# vfd.net
KiCad netlist of a schematic drawn in EAGLE
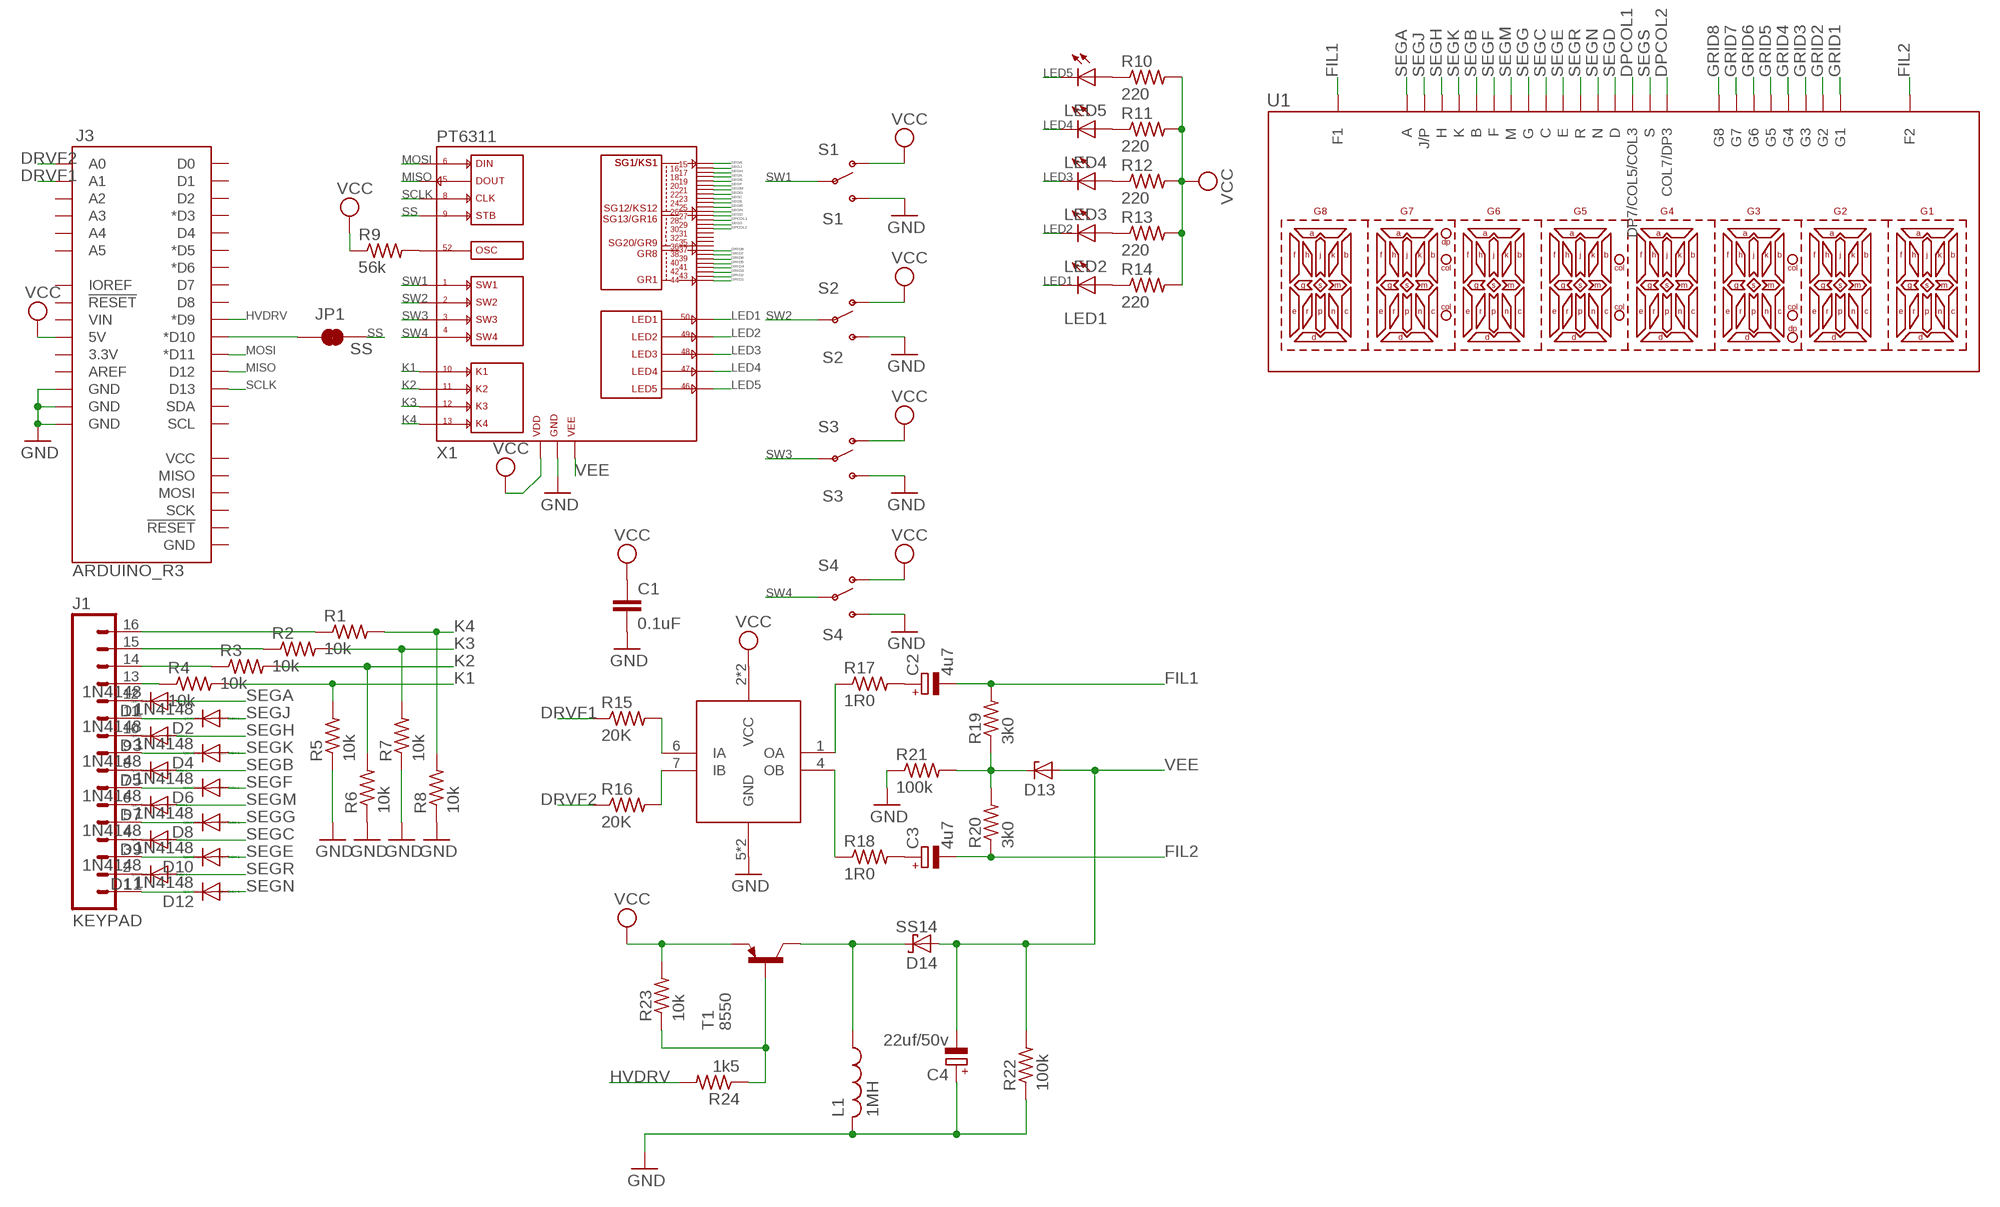
[diagram p0: schematic, sheet 1]

(export (version "E")
  (design (tool "Eeschema 10.0.6"))
  (components
    (comp (ref "C1")
      (value "0.1uF")
      (footprint "eagle-import:C050-025X075")
      (libsource (lib "eagle-import") (part "C-EU050-025X075"))
    )
    (comp (ref "C2")
      (value "4u7")
      (footprint "eagle-import:B45181A")
      (libsource (lib "eagle-import") (part "CPOL-EUB45181A"))
    )
    (comp (ref "C3")
      (value "4u7")
      (footprint "eagle-import:B45181A")
      (libsource (lib "eagle-import") (part "CPOL-EUB45181A"))
    )
    (comp (ref "C4")
      (value "22uf/50v")
      (footprint "eagle-import:B45181A")
      (libsource (lib "eagle-import") (part "CPOL-EUB45181A"))
    )
    (comp (ref "D1")
      (value "1N4148")
      (footprint "eagle-import:D-5")
      (libsource (lib "eagle-import") (part "DIODE-D-5"))
    )
    (comp (ref "D2")
      (value "1N4148")
      (footprint "eagle-import:D-5")
      (libsource (lib "eagle-import") (part "DIODE-D-5"))
    )
    (comp (ref "D3")
      (value "1N4148")
      (footprint "eagle-import:D-5")
      (libsource (lib "eagle-import") (part "DIODE-D-5"))
    )
    (comp (ref "D4")
      (value "1N4148")
      (footprint "eagle-import:D-5")
      (libsource (lib "eagle-import") (part "DIODE-D-5"))
    )
    (comp (ref "D5")
      (value "1N4148")
      (footprint "eagle-import:D-5")
      (libsource (lib "eagle-import") (part "DIODE-D-5"))
    )
    (comp (ref "D6")
      (value "1N4148")
      (footprint "eagle-import:D-5")
      (libsource (lib "eagle-import") (part "DIODE-D-5"))
    )
    (comp (ref "D7")
      (value "1N4148")
      (footprint "eagle-import:D-5")
      (libsource (lib "eagle-import") (part "DIODE-D-5"))
    )
    (comp (ref "D8")
      (value "1N4148")
      (footprint "eagle-import:D-5")
      (libsource (lib "eagle-import") (part "DIODE-D-5"))
    )
    (comp (ref "D9")
      (value "1N4148")
      (footprint "eagle-import:D-5")
      (libsource (lib "eagle-import") (part "DIODE-D-5"))
    )
    (comp (ref "D10")
      (value "1N4148")
      (footprint "eagle-import:D-5")
      (libsource (lib "eagle-import") (part "DIODE-D-5"))
    )
    (comp (ref "D11")
      (value "1N4148")
      (footprint "eagle-import:D-5")
      (libsource (lib "eagle-import") (part "DIODE-D-5"))
    )
    (comp (ref "D12")
      (value "1N4148")
      (footprint "eagle-import:D-5")
      (libsource (lib "eagle-import") (part "DIODE-D-5"))
    )
    (comp (ref "D13")
      (value "ZENER-DIODEDO34-7")
      (footprint "eagle-import:DO34Z7")
      (libsource (lib "eagle-import") (part "ZENER-DIODEDO34-7"))
    )
    (comp (ref "D14")
      (value "SS14")
      (footprint "eagle-import:DO35-7")
      (libsource (lib "eagle-import") (part "SCHOTTKY-DIODEDO35-7"))
    )
    (comp (ref "J1")
      (value "KEYPAD")
      (footprint "eagle-import:1X16")
      (libsource (lib "eagle-import") (part "M16PTH"))
    )
    (comp (ref "J3")
      (value "ARDUINO_R3")
      (footprint "eagle-import:ARDUINO_R3")
      (libsource (lib "eagle-import") (part "ARDUINO_R3"))
    )
    (comp (ref "JP1")
      (value "SS")
      (footprint "eagle-import:PAD-JUMPER-2-NC_BY_TRACE_YES_SILK")
      (libsource (lib "eagle-import") (part "JUMPER-PAD-2-NC_BY_TRACE"))
    )
    (comp (ref "L1")
      (value "1MH")
      (footprint "eagle-import:0204_5")
      (libsource (lib "eagle-import") (part "L-US0204/5"))
    )
    (comp (ref "LED1")
      (value "LED1")
      (footprint "eagle-import:LED3MM")
      (libsource (lib "eagle-import") (part "LED3MM"))
    )
    (comp (ref "LED2")
      (value "LED2")
      (footprint "eagle-import:LED3MM")
      (libsource (lib "eagle-import") (part "LED3MM"))
    )
    (comp (ref "LED3")
      (value "LED3")
      (footprint "eagle-import:LED3MM")
      (libsource (lib "eagle-import") (part "LED3MM"))
    )
    (comp (ref "LED4")
      (value "LED4")
      (footprint "eagle-import:LED3MM")
      (libsource (lib "eagle-import") (part "LED3MM"))
    )
    (comp (ref "LED5")
      (value "LED5")
      (footprint "eagle-import:LED3MM")
      (libsource (lib "eagle-import") (part "LED3MM"))
    )
    (comp (ref "R1")
      (value "10k")
      (footprint "eagle-import:0204_7")
      (libsource (lib "eagle-import") (part "R-US_0204/7"))
    )
    (comp (ref "R2")
      (value "10k")
      (footprint "eagle-import:0204_7")
      (libsource (lib "eagle-import") (part "R-US_0204/7"))
    )
    (comp (ref "R3")
      (value "10k")
      (footprint "eagle-import:0204_7")
      (libsource (lib "eagle-import") (part "R-US_0204/7"))
    )
    (comp (ref "R4")
      (value "10k")
      (footprint "eagle-import:0204_7")
      (libsource (lib "eagle-import") (part "R-US_0204/7"))
    )
    (comp (ref "R5")
      (value "10k")
      (footprint "eagle-import:0204_5")
      (libsource (lib "eagle-import") (part "R-US_0204/5"))
    )
    (comp (ref "R6")
      (value "10k")
      (footprint "eagle-import:0204_5")
      (libsource (lib "eagle-import") (part "R-US_0204/5"))
    )
    (comp (ref "R7")
      (value "10k")
      (footprint "eagle-import:0204_5")
      (libsource (lib "eagle-import") (part "R-US_0204/5"))
    )
    (comp (ref "R8")
      (value "10k")
      (footprint "eagle-import:0204_5")
      (libsource (lib "eagle-import") (part "R-US_0204/5"))
    )
    (comp (ref "R9")
      (value "56k")
      (footprint "eagle-import:0204_5")
      (libsource (lib "eagle-import") (part "R-US_0204/5"))
    )
    (comp (ref "R10")
      (value "220")
      (footprint "eagle-import:0204_5")
      (libsource (lib "eagle-import") (part "R-US_0204/5"))
    )
    (comp (ref "R11")
      (value "220")
      (footprint "eagle-import:0204_5")
      (libsource (lib "eagle-import") (part "R-US_0204/5"))
    )
    (comp (ref "R12")
      (value "220")
      (footprint "eagle-import:0204_5")
      (libsource (lib "eagle-import") (part "R-US_0204/5"))
    )
    (comp (ref "R13")
      (value "220")
      (footprint "eagle-import:0204_5")
      (libsource (lib "eagle-import") (part "R-US_0204/5"))
    )
    (comp (ref "R14")
      (value "220")
      (footprint "eagle-import:0204_5")
      (libsource (lib "eagle-import") (part "R-US_0204/5"))
    )
    (comp (ref "R15")
      (value "20K")
      (footprint "eagle-import:0204_5")
      (libsource (lib "eagle-import") (part "R-US_0204/5"))
    )
    (comp (ref "R16")
      (value "20K")
      (footprint "eagle-import:0204_5")
      (libsource (lib "eagle-import") (part "R-US_0204/5"))
    )
    (comp (ref "R17")
      (value "1R0")
      (footprint "eagle-import:0204_5")
      (libsource (lib "eagle-import") (part "R-US_0204/5"))
    )
    (comp (ref "R18")
      (value "1R0")
      (footprint "eagle-import:0204_5")
      (libsource (lib "eagle-import") (part "R-US_0204/5"))
    )
    (comp (ref "R19")
      (value "3k0")
      (footprint "eagle-import:0204_7")
      (libsource (lib "eagle-import") (part "R-US_0204/7"))
    )
    (comp (ref "R20")
      (value "3k0")
      (footprint "eagle-import:0204_7")
      (libsource (lib "eagle-import") (part "R-US_0204/7"))
    )
    (comp (ref "R21")
      (value "100k")
      (footprint "eagle-import:0204_7")
      (libsource (lib "eagle-import") (part "R-US_0204/7"))
    )
    (comp (ref "R22")
      (value "100k")
      (footprint "eagle-import:0204_5")
      (libsource (lib "eagle-import") (part "R-US_0204/5"))
    )
    (comp (ref "R23")
      (value "10k")
      (footprint "eagle-import:0204_5")
      (libsource (lib "eagle-import") (part "R-US_0204/5"))
    )
    (comp (ref "R24")
      (value "1k5")
      (footprint "eagle-import:0204_5")
      (libsource (lib "eagle-import") (part "R-US_0204/5"))
    )
    (comp (ref "S1")
      (value "S1")
      (footprint "eagle-import:SWITCH-SPDT")
      (libsource (lib "eagle-import") (part "SWITCH-SPDTPTH"))
    )
    (comp (ref "S2")
      (value "S2")
      (footprint "eagle-import:SWITCH-SPDT")
      (libsource (lib "eagle-import") (part "SWITCH-SPDTPTH"))
    )
    (comp (ref "S3")
      (value "S3")
      (footprint "eagle-import:SWITCH-SPDT")
      (libsource (lib "eagle-import") (part "SWITCH-SPDTPTH"))
    )
    (comp (ref "S4")
      (value "S4")
      (footprint "eagle-import:SWITCH-SPDT")
      (libsource (lib "eagle-import") (part "SWITCH-SPDTPTH"))
    )
    (comp (ref "T1")
      (value "8550")
      (footprint "eagle-import:TO92")
      (libsource (lib "eagle-import") (part "-PNP-TO92"))
    )
    (comp (ref "U$1")
      (value "L9110")
      (footprint "eagle-import:SOP8-1.27-5X3.6MM")
      (libsource (lib "eagle-import") (part "L9110"))
    )
    (comp (ref "U1")
      (value "20070-1A04PTH")
      (footprint "eagle-import:20070-1A04")
      (libsource (lib "eagle-import") (part "20070-1A04PTH"))
    )
    (comp (ref "X1")
      (value "DRV")
      (footprint "eagle-import:QFP52")
      (libsource (lib "eagle-import") (part "PT6311"))
    )
  )
  (nets
    (net (code "1") (name "/DPCOL1") (class "Default")
      (node (ref "U1") (pin "17") (pinfunction "DP7/COL5/COL3_17") (pintype "bidirectional"))
      (node (ref "X1") (pin "P$28") (pinfunction "SG14/GR15_P$28") (pintype "bidirectional"))
    )
    (net (code "2") (name "/DPCOL2") (class "Default")
      (node (ref "U1") (pin "19") (pinfunction "COL7/DP3_19") (pintype "bidirectional"))
      (node (ref "X1") (pin "P$30") (pinfunction "SG16/GR13_P$30") (pintype "bidirectional"))
    )
    (net (code "3") (name "/DRVF1") (class "Default")
      (node (ref "J3") (pin "A1") (pinfunction "A1_A1") (pintype "bidirectional"))
      (node (ref "R15") (pin "1") (pinfunction "1_1") (pintype "passive"))
    )
    (net (code "4") (name "/DRVF2") (class "Default")
      (node (ref "J3") (pin "A0") (pinfunction "A0_A0") (pintype "bidirectional"))
      (node (ref "R16") (pin "1") (pinfunction "1_1") (pintype "passive"))
    )
    (net (code "5") (name "/FIL1") (class "Default")
      (node (ref "C2") (pin "-") (pinfunction "-_-") (pintype "passive"))
      (node (ref "R19") (pin "2") (pinfunction "2_2") (pintype "passive"))
      (node (ref "U1") (pin "1") (pinfunction "F1_1") (pintype "bidirectional"))
      (node (ref "U1") (pin "2") (pinfunction "F1_2") (pintype "bidirectional"))
    )
    (net (code "6") (name "/FIL2") (class "Default")
      (node (ref "C3") (pin "-") (pinfunction "-_-") (pintype "passive"))
      (node (ref "R20") (pin "1") (pinfunction "1_1") (pintype "passive"))
      (node (ref "U1") (pin "29") (pinfunction "F2_29") (pintype "bidirectional"))
      (node (ref "U1") (pin "30") (pinfunction "F2_30") (pintype "bidirectional"))
    )
    (net (code "7") (name "/GRID1") (class "Default")
      (node (ref "U1") (pin "27") (pinfunction "G1_27") (pintype "bidirectional"))
      (node (ref "X1") (pin "P$44") (pinfunction "GR1_P$44") (pintype "bidirectional"))
    )
    (net (code "8") (name "/GRID2") (class "Default")
      (node (ref "U1") (pin "26") (pinfunction "G2_26") (pintype "bidirectional"))
      (node (ref "X1") (pin "P$43") (pinfunction "GR2_P$43") (pintype "bidirectional"))
    )
    (net (code "9") (name "/GRID3") (class "Default")
      (node (ref "U1") (pin "25") (pinfunction "G3_25") (pintype "bidirectional"))
      (node (ref "X1") (pin "P$42") (pinfunction "GR3_P$42") (pintype "bidirectional"))
    )
    (net (code "10") (name "/GRID4") (class "Default")
      (node (ref "U1") (pin "24") (pinfunction "G4_24") (pintype "bidirectional"))
      (node (ref "X1") (pin "P$41") (pinfunction "GR4_P$41") (pintype "bidirectional"))
    )
    (net (code "11") (name "/GRID5") (class "Default")
      (node (ref "U1") (pin "23") (pinfunction "G5_23") (pintype "bidirectional"))
      (node (ref "X1") (pin "P$40") (pinfunction "GR5_P$40") (pintype "bidirectional"))
    )
    (net (code "12") (name "/GRID6") (class "Default")
      (node (ref "U1") (pin "22") (pinfunction "G6_22") (pintype "bidirectional"))
      (node (ref "X1") (pin "P$39") (pinfunction "GR6_P$39") (pintype "bidirectional"))
    )
    (net (code "13") (name "/GRID7") (class "Default")
      (node (ref "U1") (pin "21") (pinfunction "G7_21") (pintype "bidirectional"))
      (node (ref "X1") (pin "P$38") (pinfunction "GR7_P$38") (pintype "bidirectional"))
    )
    (net (code "14") (name "/GRID8") (class "Default")
      (node (ref "U1") (pin "20") (pinfunction "G8_20") (pintype "bidirectional"))
      (node (ref "X1") (pin "P$37") (pinfunction "GR8_P$37") (pintype "bidirectional"))
    )
    (net (code "15") (name "/HVDRV") (class "Default")
      (node (ref "J3") (pin "D9") (pinfunction "*D9_D9") (pintype "bidirectional"))
      (node (ref "R24") (pin "2") (pinfunction "2_2") (pintype "passive"))
    )
    (net (code "16") (name "/K1") (class "Default")
      (node (ref "R4") (pin "2") (pinfunction "2_2") (pintype "passive"))
      (node (ref "R5") (pin "2") (pinfunction "2_2") (pintype "passive"))
      (node (ref "X1") (pin "P$10") (pinfunction "K1_P$10") (pintype "bidirectional"))
    )
    (net (code "17") (name "/K2") (class "Default")
      (node (ref "R3") (pin "2") (pinfunction "2_2") (pintype "passive"))
      (node (ref "R6") (pin "2") (pinfunction "2_2") (pintype "passive"))
      (node (ref "X1") (pin "P$11") (pinfunction "K2_P$11") (pintype "bidirectional"))
    )
    (net (code "18") (name "/K3") (class "Default")
      (node (ref "R2") (pin "2") (pinfunction "2_2") (pintype "passive"))
      (node (ref "R7") (pin "2") (pinfunction "2_2") (pintype "passive"))
      (node (ref "X1") (pin "P$12") (pinfunction "K3_P$12") (pintype "bidirectional"))
    )
    (net (code "19") (name "/K4") (class "Default")
      (node (ref "R1") (pin "2") (pinfunction "2_2") (pintype "passive"))
      (node (ref "R8") (pin "2") (pinfunction "2_2") (pintype "passive"))
      (node (ref "X1") (pin "P$13") (pinfunction "K4_P$13") (pintype "bidirectional"))
    )
    (net (code "20") (name "/LED1") (class "Default")
      (node (ref "LED1") (pin "K") (pinfunction "C_K") (pintype "passive"))
      (node (ref "X1") (pin "P$50") (pinfunction "LED1_P$50") (pintype "bidirectional"))
    )
    (net (code "21") (name "/LED2") (class "Default")
      (node (ref "LED2") (pin "K") (pinfunction "C_K") (pintype "passive"))
      (node (ref "X1") (pin "P$49") (pinfunction "LED2_P$49") (pintype "bidirectional"))
    )
    (net (code "22") (name "/LED3") (class "Default")
      (node (ref "LED3") (pin "K") (pinfunction "C_K") (pintype "passive"))
      (node (ref "X1") (pin "P$48") (pinfunction "LED3_P$48") (pintype "bidirectional"))
    )
    (net (code "23") (name "/LED4") (class "Default")
      (node (ref "LED4") (pin "K") (pinfunction "C_K") (pintype "passive"))
      (node (ref "X1") (pin "P$47") (pinfunction "LED4_P$47") (pintype "bidirectional"))
    )
    (net (code "24") (name "/LED5") (class "Default")
      (node (ref "LED5") (pin "K") (pinfunction "C_K") (pintype "passive"))
      (node (ref "X1") (pin "P$46") (pinfunction "LED5_P$46") (pintype "bidirectional"))
    )
    (net (code "25") (name "/MISO") (class "Default")
      (node (ref "J3") (pin "D12") (pinfunction "D12_D12") (pintype "bidirectional"))
      (node (ref "X1") (pin "P$5") (pinfunction "DOUT_P$5") (pintype "bidirectional"))
    )
    (net (code "26") (name "/MOSI") (class "Default")
      (node (ref "J3") (pin "D11") (pinfunction "*D11_D11") (pintype "bidirectional"))
      (node (ref "X1") (pin "P$6") (pinfunction "DIN_P$6") (pintype "bidirectional"))
    )
    (net (code "27") (name "/SCLK") (class "Default")
      (node (ref "J3") (pin "D13") (pinfunction "D13_D13") (pintype "bidirectional"))
      (node (ref "X1") (pin "P$8") (pinfunction "CLK_P$8") (pintype "bidirectional"))
    )
    (net (code "28") (name "/SEGA") (class "Default")
      (node (ref "D1") (pin "A") (pinfunction "A_A") (pintype "passive"))
      (node (ref "U1") (pin "4") (pinfunction "A_4") (pintype "bidirectional"))
      (node (ref "X1") (pin "P$15") (pinfunction "SG1/KS1_P$15") (pintype "bidirectional"))
    )
    (net (code "29") (name "/SEGB") (class "Default")
      (node (ref "D5") (pin "A") (pinfunction "A_A") (pintype "passive"))
      (node (ref "U1") (pin "8") (pinfunction "B_8") (pintype "bidirectional"))
      (node (ref "X1") (pin "P$19") (pinfunction "SG5/KS5_P$19") (pintype "bidirectional"))
    )
    (net (code "30") (name "/SEGC") (class "Default")
      (node (ref "D9") (pin "A") (pinfunction "A_A") (pintype "passive"))
      (node (ref "U1") (pin "12") (pinfunction "C_12") (pintype "bidirectional"))
      (node (ref "X1") (pin "P$23") (pinfunction "SG9/KS9_P$23") (pintype "bidirectional"))
    )
    (net (code "31") (name "/SEGD") (class "Default")
      (node (ref "U1") (pin "16") (pinfunction "D_16") (pintype "bidirectional"))
      (node (ref "X1") (pin "P$27") (pinfunction "SG13/GR16_P$27") (pintype "bidirectional"))
    )
    (net (code "32") (name "/SEGE") (class "Default")
      (node (ref "D10") (pin "A") (pinfunction "A_A") (pintype "passive"))
      (node (ref "U1") (pin "13") (pinfunction "E_13") (pintype "bidirectional"))
      (node (ref "X1") (pin "P$24") (pinfunction "SG10/KS10_P$24") (pintype "bidirectional"))
    )
    (net (code "33") (name "/SEGF") (class "Default")
      (node (ref "D6") (pin "A") (pinfunction "A_A") (pintype "passive"))
      (node (ref "U1") (pin "9") (pinfunction "F_9") (pintype "bidirectional"))
      (node (ref "X1") (pin "P$20") (pinfunction "SG6/KS6_P$20") (pintype "bidirectional"))
    )
    (net (code "34") (name "/SEGG") (class "Default")
      (node (ref "D8") (pin "A") (pinfunction "A_A") (pintype "passive"))
      (node (ref "U1") (pin "11") (pinfunction "G_11") (pintype "bidirectional"))
      (node (ref "X1") (pin "P$22") (pinfunction "SG8/KS8_P$22") (pintype "bidirectional"))
    )
    (net (code "35") (name "/SEGH") (class "Default")
      (node (ref "D3") (pin "A") (pinfunction "A_A") (pintype "passive"))
      (node (ref "U1") (pin "6") (pinfunction "H_6") (pintype "bidirectional"))
      (node (ref "X1") (pin "P$17") (pinfunction "SG3/KS3_P$17") (pintype "bidirectional"))
    )
    (net (code "36") (name "/SEGJ") (class "Default")
      (node (ref "D2") (pin "A") (pinfunction "A_A") (pintype "passive"))
      (node (ref "U1") (pin "5") (pinfunction "J/P_5") (pintype "bidirectional"))
      (node (ref "X1") (pin "P$16") (pinfunction "SG2/KS2_P$16") (pintype "bidirectional"))
    )
    (net (code "37") (name "/SEGK") (class "Default")
      (node (ref "D4") (pin "A") (pinfunction "A_A") (pintype "passive"))
      (node (ref "U1") (pin "7") (pinfunction "K_7") (pintype "bidirectional"))
      (node (ref "X1") (pin "P$18") (pinfunction "SG4/KS4_P$18") (pintype "bidirectional"))
    )
    (net (code "38") (name "/SEGM") (class "Default")
      (node (ref "D7") (pin "A") (pinfunction "A_A") (pintype "passive"))
      (node (ref "U1") (pin "10") (pinfunction "M_10") (pintype "bidirectional"))
      (node (ref "X1") (pin "P$21") (pinfunction "SG7/KS7_P$21") (pintype "bidirectional"))
    )
    (net (code "39") (name "/SEGN") (class "Default")
      (node (ref "D12") (pin "A") (pinfunction "A_A") (pintype "passive"))
      (node (ref "U1") (pin "15") (pinfunction "N_15") (pintype "bidirectional"))
      (node (ref "X1") (pin "P$26") (pinfunction "SG12/KS12_P$26") (pintype "bidirectional"))
    )
    (net (code "40") (name "/SEGR") (class "Default")
      (node (ref "D11") (pin "A") (pinfunction "A_A") (pintype "passive"))
      (node (ref "U1") (pin "14") (pinfunction "R_14") (pintype "bidirectional"))
      (node (ref "X1") (pin "P$25") (pinfunction "SG11/KS11_P$25") (pintype "bidirectional"))
    )
    (net (code "41") (name "/SEGS") (class "Default")
      (node (ref "U1") (pin "18") (pinfunction "S_18") (pintype "bidirectional"))
      (node (ref "X1") (pin "P$29") (pinfunction "SG15/GR14_P$29") (pintype "bidirectional"))
    )
    (net (code "42") (name "/SS") (class "Default")
      (node (ref "JP1") (pin "2") (pinfunction "2_2") (pintype "passive"))
      (node (ref "X1") (pin "P$9") (pinfunction "STB_P$9") (pintype "bidirectional"))
    )
    (net (code "43") (name "/SW1") (class "Default")
      (node (ref "S1") (pin "2") (pinfunction "P_2") (pintype "passive"))
      (node (ref "X1") (pin "P$1") (pinfunction "SW1_P$1") (pintype "bidirectional"))
    )
    (net (code "44") (name "/SW2") (class "Default")
      (node (ref "S2") (pin "2") (pinfunction "P_2") (pintype "passive"))
      (node (ref "X1") (pin "P$2") (pinfunction "SW2_P$2") (pintype "bidirectional"))
    )
    (net (code "45") (name "/SW3") (class "Default")
      (node (ref "S3") (pin "2") (pinfunction "P_2") (pintype "passive"))
      (node (ref "X1") (pin "P$3") (pinfunction "SW3_P$3") (pintype "bidirectional"))
    )
    (net (code "46") (name "/SW4") (class "Default")
      (node (ref "S4") (pin "2") (pinfunction "P_2") (pintype "passive"))
      (node (ref "X1") (pin "P$4") (pinfunction "SW4_P$4") (pintype "bidirectional"))
    )
    (net (code "47") (name "/VEE") (class "Default")
      (node (ref "C4") (pin "-") (pinfunction "-_-") (pintype "passive"))
      (node (ref "D13") (pin "A") (pinfunction "A_A") (pintype "passive"))
      (node (ref "D14") (pin "A") (pinfunction "A_A") (pintype "passive"))
      (node (ref "R22") (pin "2") (pinfunction "2_2") (pintype "passive"))
      (node (ref "X1") (pin "P$34") (pinfunction "VEE_P$34") (pintype "bidirectional"))
    )
    (net (code "48") (name "GND") (class "Default")
      (node (ref "C1") (pin "2") (pinfunction "2_2") (pintype "passive"))
      (node (ref "C4") (pin "+") (pinfunction "+_+") (pintype "passive"))
      (node (ref "J3") (pin "GND@2") (pinfunction "GND_GND@2") (pintype "bidirectional"))
      (node (ref "J3") (pin "GND@3") (pinfunction "GND_GND@3") (pintype "bidirectional"))
      (node (ref "J3") (pin "GND@4") (pinfunction "GND_GND@4") (pintype "bidirectional"))
      (node (ref "L1") (pin "2") (pinfunction "2_2") (pintype "passive"))
      (node (ref "R21") (pin "1") (pinfunction "1_1") (pintype "passive"))
      (node (ref "R22") (pin "1") (pinfunction "1_1") (pintype "passive"))
      (node (ref "R5") (pin "1") (pinfunction "1_1") (pintype "passive"))
      (node (ref "R6") (pin "1") (pinfunction "1_1") (pintype "passive"))
      (node (ref "R7") (pin "1") (pinfunction "1_1") (pintype "passive"))
      (node (ref "R8") (pin "1") (pinfunction "1_1") (pintype "passive"))
      (node (ref "S1") (pin "3") (pinfunction "S_3") (pintype "passive"))
      (node (ref "S2") (pin "3") (pinfunction "S_3") (pintype "passive"))
      (node (ref "S3") (pin "3") (pinfunction "S_3") (pintype "passive"))
      (node (ref "S4") (pin "3") (pinfunction "S_3") (pintype "passive"))
      (node (ref "U$1") (pin "5") (pinfunction "GND_5") (pintype "bidirectional"))
      (node (ref "U$1") (pin "8") (pinfunction "GND_8") (pintype "bidirectional"))
      (node (ref "X1") (pin "P$51") (pinfunction "GND_P$51") (pintype "bidirectional"))
    )
    (net (code "49") (name "Net-(C2-Pad+)") (class "Default")
      (node (ref "C2") (pin "+") (pinfunction "+_+") (pintype "passive"))
      (node (ref "R17") (pin "2") (pinfunction "2_2") (pintype "passive"))
    )
    (net (code "50") (name "Net-(C3-Pad+)") (class "Default")
      (node (ref "C3") (pin "+") (pinfunction "+_+") (pintype "passive"))
      (node (ref "R18") (pin "2") (pinfunction "2_2") (pintype "passive"))
    )
    (net (code "51") (name "Net-(D1-PadC)") (class "Default")
      (node (ref "D1") (pin "C") (pinfunction "C_C") (pintype "passive"))
      (node (ref "J1") (pin "12") (pinfunction "12_12") (pintype "passive"))
    )
    (net (code "52") (name "Net-(D2-PadC)") (class "Default")
      (node (ref "D2") (pin "C") (pinfunction "C_C") (pintype "passive"))
      (node (ref "J1") (pin "11") (pinfunction "11_11") (pintype "passive"))
    )
    (net (code "53") (name "Net-(D3-PadC)") (class "Default")
      (node (ref "D3") (pin "C") (pinfunction "C_C") (pintype "passive"))
      (node (ref "J1") (pin "10") (pinfunction "10_10") (pintype "passive"))
    )
    (net (code "54") (name "Net-(D4-PadC)") (class "Default")
      (node (ref "D4") (pin "C") (pinfunction "C_C") (pintype "passive"))
      (node (ref "J1") (pin "9") (pinfunction "9_9") (pintype "passive"))
    )
    (net (code "55") (name "Net-(D5-PadC)") (class "Default")
      (node (ref "D5") (pin "C") (pinfunction "C_C") (pintype "passive"))
      (node (ref "J1") (pin "8") (pinfunction "8_8") (pintype "passive"))
    )
    (net (code "56") (name "Net-(D6-PadC)") (class "Default")
      (node (ref "D6") (pin "C") (pinfunction "C_C") (pintype "passive"))
      (node (ref "J1") (pin "7") (pinfunction "7_7") (pintype "passive"))
    )
    (net (code "57") (name "Net-(D7-PadC)") (class "Default")
      (node (ref "D7") (pin "C") (pinfunction "C_C") (pintype "passive"))
      (node (ref "J1") (pin "6") (pinfunction "6_6") (pintype "passive"))
    )
    (net (code "58") (name "Net-(D8-PadC)") (class "Default")
      (node (ref "D8") (pin "C") (pinfunction "C_C") (pintype "passive"))
      (node (ref "J1") (pin "5") (pinfunction "5_5") (pintype "passive"))
    )
    (net (code "59") (name "Net-(D9-PadC)") (class "Default")
      (node (ref "D9") (pin "C") (pinfunction "C_C") (pintype "passive"))
      (node (ref "J1") (pin "4") (pinfunction "4_4") (pintype "passive"))
    )
    (net (code "60") (name "Net-(D10-PadC)") (class "Default")
      (node (ref "D10") (pin "C") (pinfunction "C_C") (pintype "passive"))
      (node (ref "J1") (pin "3") (pinfunction "3_3") (pintype "passive"))
    )
    (net (code "61") (name "Net-(D11-PadC)") (class "Default")
      (node (ref "D11") (pin "C") (pinfunction "C_C") (pintype "passive"))
      (node (ref "J1") (pin "2") (pinfunction "2_2") (pintype "passive"))
    )
    (net (code "62") (name "Net-(D12-PadC)") (class "Default")
      (node (ref "D12") (pin "C") (pinfunction "C_C") (pintype "passive"))
      (node (ref "J1") (pin "1") (pinfunction "1_1") (pintype "passive"))
    )
    (net (code "63") (name "Net-(D13-PadC)") (class "Default")
      (node (ref "D13") (pin "C") (pinfunction "C_C") (pintype "passive"))
      (node (ref "R19") (pin "1") (pinfunction "1_1") (pintype "passive"))
      (node (ref "R20") (pin "2") (pinfunction "2_2") (pintype "passive"))
      (node (ref "R21") (pin "2") (pinfunction "2_2") (pintype "passive"))
    )
    (net (code "64") (name "Net-(J1-Pad13)") (class "Default")
      (node (ref "J1") (pin "13") (pinfunction "13_13") (pintype "passive"))
      (node (ref "R4") (pin "1") (pinfunction "1_1") (pintype "passive"))
    )
    (net (code "65") (name "Net-(J1-Pad14)") (class "Default")
      (node (ref "J1") (pin "14") (pinfunction "14_14") (pintype "passive"))
      (node (ref "R3") (pin "1") (pinfunction "1_1") (pintype "passive"))
    )
    (net (code "66") (name "Net-(J1-Pad15)") (class "Default")
      (node (ref "J1") (pin "15") (pinfunction "15_15") (pintype "passive"))
      (node (ref "R2") (pin "1") (pinfunction "1_1") (pintype "passive"))
    )
    (net (code "67") (name "Net-(J1-Pad16)") (class "Default")
      (node (ref "J1") (pin "16") (pinfunction "16_16") (pintype "passive"))
      (node (ref "R1") (pin "1") (pinfunction "1_1") (pintype "passive"))
    )
    (net (code "68") (name "Net-(J3-*D10)") (class "Default")
      (node (ref "J3") (pin "D10") (pinfunction "*D10_D10") (pintype "bidirectional"))
      (node (ref "JP1") (pin "1") (pinfunction "1_1") (pintype "passive"))
    )
    (net (code "69") (name "Net-(LED1-PadA)") (class "Default")
      (node (ref "LED1") (pin "A") (pinfunction "A_A") (pintype "passive"))
      (node (ref "R14") (pin "1") (pinfunction "1_1") (pintype "passive"))
    )
    (net (code "70") (name "Net-(LED2-PadA)") (class "Default")
      (node (ref "LED2") (pin "A") (pinfunction "A_A") (pintype "passive"))
      (node (ref "R13") (pin "1") (pinfunction "1_1") (pintype "passive"))
    )
    (net (code "71") (name "Net-(LED3-PadA)") (class "Default")
      (node (ref "LED3") (pin "A") (pinfunction "A_A") (pintype "passive"))
      (node (ref "R12") (pin "1") (pinfunction "1_1") (pintype "passive"))
    )
    (net (code "72") (name "Net-(LED4-PadA)") (class "Default")
      (node (ref "LED4") (pin "A") (pinfunction "A_A") (pintype "passive"))
      (node (ref "R11") (pin "1") (pinfunction "1_1") (pintype "passive"))
    )
    (net (code "73") (name "Net-(LED5-PadA)") (class "Default")
      (node (ref "LED5") (pin "A") (pinfunction "A_A") (pintype "passive"))
      (node (ref "R10") (pin "1") (pinfunction "1_1") (pintype "passive"))
    )
    (net (code "74") (name "Net-(T1-B)") (class "Default")
      (node (ref "R23") (pin "1") (pinfunction "1_1") (pintype "passive"))
      (node (ref "R24") (pin "1") (pinfunction "1_1") (pintype "passive"))
      (node (ref "T1") (pin "2") (pinfunction "B_2") (pintype "passive"))
    )
    (net (code "75") (name "Net-(T1-C)") (class "Default")
      (node (ref "D14") (pin "C") (pinfunction "C_C") (pintype "passive"))
      (node (ref "L1") (pin "1") (pinfunction "1_1") (pintype "passive"))
      (node (ref "T1") (pin "3") (pinfunction "C_3") (pintype "passive"))
    )
    (net (code "76") (name "Net-(U$1-IA)") (class "Default")
      (node (ref "R15") (pin "2") (pinfunction "2_2") (pintype "passive"))
      (node (ref "U$1") (pin "6") (pinfunction "IA_6") (pintype "bidirectional"))
    )
    (net (code "77") (name "Net-(U$1-IB)") (class "Default")
      (node (ref "R16") (pin "2") (pinfunction "2_2") (pintype "passive"))
      (node (ref "U$1") (pin "7") (pinfunction "IB_7") (pintype "bidirectional"))
    )
    (net (code "78") (name "Net-(U$1-OA)") (class "Default")
      (node (ref "R17") (pin "1") (pinfunction "1_1") (pintype "passive"))
      (node (ref "U$1") (pin "1") (pinfunction "OA_1") (pintype "bidirectional"))
    )
    (net (code "79") (name "Net-(U$1-OB)") (class "Default")
      (node (ref "R18") (pin "1") (pinfunction "1_1") (pintype "passive"))
      (node (ref "U$1") (pin "4") (pinfunction "OB_4") (pintype "bidirectional"))
    )
    (net (code "80") (name "Net-(X1-OSC)") (class "Default")
      (node (ref "R9") (pin "2") (pinfunction "2_2") (pintype "passive"))
      (node (ref "X1") (pin "P$52") (pinfunction "OSC_P$52") (pintype "bidirectional"))
    )
    (net (code "81") (name "VCC") (class "Default")
      (node (ref "C1") (pin "1") (pinfunction "1_1") (pintype "passive"))
      (node (ref "J3") (pin "5V") (pinfunction "5V_5V") (pintype "bidirectional"))
      (node (ref "R10") (pin "2") (pinfunction "2_2") (pintype "passive"))
      (node (ref "R11") (pin "2") (pinfunction "2_2") (pintype "passive"))
      (node (ref "R12") (pin "2") (pinfunction "2_2") (pintype "passive"))
      (node (ref "R13") (pin "2") (pinfunction "2_2") (pintype "passive"))
      (node (ref "R14") (pin "2") (pinfunction "2_2") (pintype "passive"))
      (node (ref "R23") (pin "2") (pinfunction "2_2") (pintype "passive"))
      (node (ref "R9") (pin "1") (pinfunction "1_1") (pintype "passive"))
      (node (ref "S1") (pin "1") (pinfunction "O_1") (pintype "passive"))
      (node (ref "S2") (pin "1") (pinfunction "O_1") (pintype "passive"))
      (node (ref "S3") (pin "1") (pinfunction "O_1") (pintype "passive"))
      (node (ref "S4") (pin "1") (pinfunction "O_1") (pintype "passive"))
      (node (ref "T1") (pin "1") (pinfunction "E_1") (pintype "passive"))
      (node (ref "U$1") (pin "2") (pinfunction "VCC_2") (pintype "bidirectional"))
      (node (ref "U$1") (pin "3") (pinfunction "VCC_3") (pintype "bidirectional"))
      (node (ref "X1") (pin "P$14") (pinfunction "VDD_P$14") (pintype "bidirectional"))
      (node (ref "X1") (pin "P$33") (pinfunction "VDD_P$33") (pintype "bidirectional"))
      (node (ref "X1") (pin "P$45") (pinfunction "VDD_P$45") (pintype "bidirectional"))
    )
    (net (code "82") (name "unconnected-(J3-*D3-PadD3)") (class "Default")
      (node (ref "J3") (pin "D3") (pinfunction "*D3_D3") (pintype "bidirectional"))
    )
    (net (code "83") (name "unconnected-(J3-*D5-PadD5)") (class "Default")
      (node (ref "J3") (pin "D5") (pinfunction "*D5_D5") (pintype "bidirectional"))
    )
    (net (code "84") (name "unconnected-(J3-*D6-PadD6)") (class "Default")
      (node (ref "J3") (pin "D6") (pinfunction "*D6_D6") (pintype "bidirectional"))
    )
    (net (code "85") (name "unconnected-(J3-GND-PadGND@1)") (class "Default")
      (node (ref "J3") (pin "GND@1") (pinfunction "GND_GND@1") (pintype "bidirectional"))
    )
    (net (code "86") (name "unconnected-(J3-Pad3.3V)") (class "Default")
      (node (ref "J3") (pin "3.3V") (pinfunction "3.3V_3.3V") (pintype "bidirectional"))
    )
    (net (code "87") (name "unconnected-(J3-PadA2)") (class "Default")
      (node (ref "J3") (pin "A2") (pinfunction "A2_A2") (pintype "bidirectional"))
    )
    (net (code "88") (name "unconnected-(J3-PadA3)") (class "Default")
      (node (ref "J3") (pin "A3") (pinfunction "A3_A3") (pintype "bidirectional"))
    )
    (net (code "89") (name "unconnected-(J3-PadA4)") (class "Default")
      (node (ref "J3") (pin "A4") (pinfunction "A4_A4") (pintype "bidirectional"))
    )
    (net (code "90") (name "unconnected-(J3-PadA5)") (class "Default")
      (node (ref "J3") (pin "A5") (pinfunction "A5_A5") (pintype "bidirectional"))
    )
    (net (code "91") (name "unconnected-(J3-PadAREF)") (class "Default")
      (node (ref "J3") (pin "AREF") (pinfunction "AREF_AREF") (pintype "bidirectional"))
    )
    (net (code "92") (name "unconnected-(J3-PadD0)") (class "Default")
      (node (ref "J3") (pin "D0") (pinfunction "D0_D0") (pintype "bidirectional"))
    )
    (net (code "93") (name "unconnected-(J3-PadD1)") (class "Default")
      (node (ref "J3") (pin "D1") (pinfunction "D1_D1") (pintype "bidirectional"))
    )
    (net (code "94") (name "unconnected-(J3-PadD2)") (class "Default")
      (node (ref "J3") (pin "D2") (pinfunction "D2_D2") (pintype "bidirectional"))
    )
    (net (code "95") (name "unconnected-(J3-PadD4)") (class "Default")
      (node (ref "J3") (pin "D4") (pinfunction "D4_D4") (pintype "bidirectional"))
    )
    (net (code "96") (name "unconnected-(J3-PadD7)") (class "Default")
      (node (ref "J3") (pin "D7") (pinfunction "D7_D7") (pintype "bidirectional"))
    )
    (net (code "97") (name "unconnected-(J3-PadD8)") (class "Default")
      (node (ref "J3") (pin "D8") (pinfunction "D8_D8") (pintype "bidirectional"))
    )
    (net (code "98") (name "unconnected-(J3-PadIOREF)") (class "Default")
      (node (ref "J3") (pin "IOREF") (pinfunction "IOREF_IOREF") (pintype "bidirectional"))
    )
    (net (code "99") (name "unconnected-(J3-PadMISO)") (class "Default")
      (node (ref "J3") (pin "MISO") (pinfunction "MISO_MISO") (pintype "bidirectional"))
    )
    (net (code "100") (name "unconnected-(J3-PadMOSI)") (class "Default")
      (node (ref "J3") (pin "MOSI") (pinfunction "MOSI_MOSI") (pintype "bidirectional"))
    )
    (net (code "101") (name "unconnected-(J3-PadSCK)") (class "Default")
      (node (ref "J3") (pin "SCK") (pinfunction "SCK_SCK") (pintype "bidirectional"))
    )
    (net (code "102") (name "unconnected-(J3-PadSCL)") (class "Default")
      (node (ref "J3") (pin "SCL") (pinfunction "SCL_SCL") (pintype "bidirectional"))
    )
    (net (code "103") (name "unconnected-(J3-PadSDA)") (class "Default")
      (node (ref "J3") (pin "SDA") (pinfunction "SDA_SDA") (pintype "bidirectional"))
    )
    (net (code "104") (name "unconnected-(J3-PadVCC)") (class "Default")
      (node (ref "J3") (pin "VCC") (pinfunction "VCC_VCC") (pintype "bidirectional"))
    )
    (net (code "105") (name "unconnected-(J3-PadVIN)") (class "Default")
      (node (ref "J3") (pin "VIN") (pinfunction "VIN_VIN") (pintype "bidirectional"))
    )
    (net (code "106") (name "unconnected-(J3-~{RESET}-PadRESET@1)") (class "Default")
      (node (ref "J3") (pin "RESET@1") (pinfunction "~{RESET}_RESET@1") (pintype "bidirectional"))
    )
    (net (code "107") (name "unconnected-(J3-~{RESET}-PadRESET@2)") (class "Default")
      (node (ref "J3") (pin "RESET@2") (pinfunction "~{RESET}_RESET@2") (pintype "bidirectional"))
    )
    (net (code "108") (name "unconnected-(X1-SG17{slash}GR12-PadP$31)") (class "Default")
      (node (ref "X1") (pin "P$31") (pinfunction "SG17/GR12_P$31") (pintype "bidirectional"))
    )
    (net (code "109") (name "unconnected-(X1-SG18{slash}GR11-PadP$32)") (class "Default")
      (node (ref "X1") (pin "P$32") (pinfunction "SG18/GR11_P$32") (pintype "bidirectional"))
    )
    (net (code "110") (name "unconnected-(X1-SG19{slash}GR10-PadP$35)") (class "Default")
      (node (ref "X1") (pin "P$35") (pinfunction "SG19/GR10_P$35") (pintype "bidirectional"))
    )
    (net (code "111") (name "unconnected-(X1-SG20{slash}GR9-PadP$36)") (class "Default")
      (node (ref "X1") (pin "P$36") (pinfunction "SG20/GR9_P$36") (pintype "bidirectional"))
    )
  )
)
